# main.net
KiCad netlist of a schematic drawn in Altium Designer
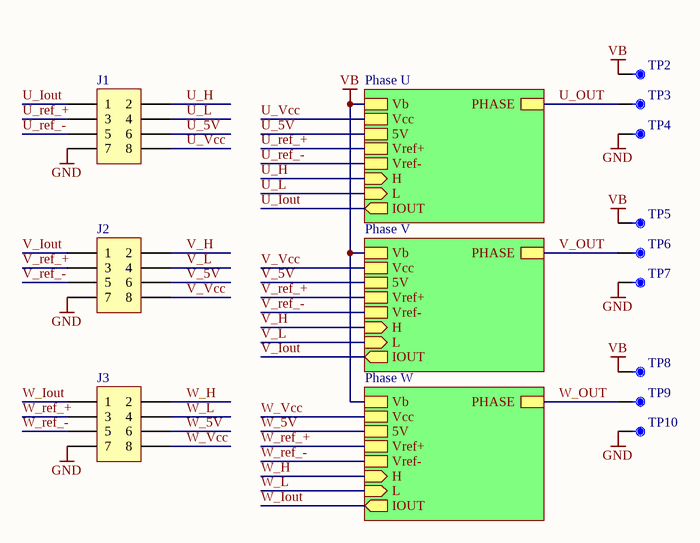
[diagram p0: main.SchDoc]

(export (version "E")
  (design (tool "Eeschema 10.0.6"))
  (components
    (comp (ref "J1")
      (value "~")
      (footprint "HDR-SMD_8P-P2.54-V-M-R2-C4-LS8.0")
      (libsource (lib "Schlib1") (part "Header 8"))
    )
    (comp (ref "J2")
      (value "~")
      (footprint "HDR-SMD_8P-P2.54-V-M-R2-C4-LS8.0")
      (libsource (lib "Schlib1") (part "Header 8"))
    )
    (comp (ref "J3")
      (value "~")
      (footprint "HDR-SMD_8P-P2.54-V-M-R2-C4-LS8.0")
      (libsource (lib "Schlib1") (part "Header 8"))
    )
    (comp (ref "TP2")
      (value "~")
      (footprint "TP2030_SMD")
      (libsource (lib "Miscellaneous Devices") (part "TP_Dup1"))
    )
    (comp (ref "TP3")
      (value "~")
      (footprint "TP2030_SMD")
      (libsource (lib "Miscellaneous Devices") (part "TP_Dup1"))
    )
    (comp (ref "TP4")
      (value "~")
      (footprint "TP2030_SMD")
      (libsource (lib "Miscellaneous Devices") (part "TP_Dup1"))
    )
    (comp (ref "TP5")
      (value "~")
      (footprint "TP2030_SMD")
      (libsource (lib "Miscellaneous Devices") (part "TP_Dup1"))
    )
    (comp (ref "TP6")
      (value "~")
      (footprint "TP2030_SMD")
      (libsource (lib "Miscellaneous Devices") (part "TP_Dup1"))
    )
    (comp (ref "TP7")
      (value "~")
      (footprint "TP2030_SMD")
      (libsource (lib "Miscellaneous Devices") (part "TP_Dup1"))
    )
    (comp (ref "TP8")
      (value "~")
      (footprint "TP2030_SMD")
      (libsource (lib "Miscellaneous Devices") (part "TP_Dup1"))
    )
    (comp (ref "TP9")
      (value "~")
      (footprint "TP2030_SMD")
      (libsource (lib "Miscellaneous Devices") (part "TP_Dup1"))
    )
    (comp (ref "TP10")
      (value "~")
      (footprint "TP2030_SMD")
      (libsource (lib "Miscellaneous Devices") (part "TP_Dup1"))
    )
  )
  (nets
    (net (code "1") (name "/U_5V") (class "Default")
      (node (ref "J1") (pin "6") (pinfunction "6_6") (pintype "passive"))
    )
    (net (code "2") (name "/U_H") (class "Default")
      (node (ref "J1") (pin "2") (pinfunction "2_2") (pintype "passive"))
    )
    (net (code "3") (name "/U_Iout") (class "Default")
      (node (ref "J1") (pin "1") (pinfunction "1_1") (pintype "passive"))
    )
    (net (code "4") (name "/U_L") (class "Default")
      (node (ref "J1") (pin "4") (pinfunction "4_4") (pintype "passive"))
    )
    (net (code "5") (name "/U_OUT") (class "Default")
      (node (ref "TP3") (pin "1") (pinfunction "1_1") (pintype "passive"))
    )
    (net (code "6") (name "/U_Vcc") (class "Default")
      (node (ref "J1") (pin "8") (pinfunction "8_8") (pintype "passive"))
    )
    (net (code "7") (name "/U_ref_+") (class "Default")
      (node (ref "J1") (pin "3") (pinfunction "3_3") (pintype "passive"))
    )
    (net (code "8") (name "/U_ref_-") (class "Default")
      (node (ref "J1") (pin "5") (pinfunction "5_5") (pintype "passive"))
    )
    (net (code "9") (name "/V_5V") (class "Default")
      (node (ref "J2") (pin "6") (pinfunction "6_6") (pintype "passive"))
    )
    (net (code "10") (name "/V_H") (class "Default")
      (node (ref "J2") (pin "2") (pinfunction "2_2") (pintype "passive"))
    )
    (net (code "11") (name "/V_Iout") (class "Default")
      (node (ref "J2") (pin "1") (pinfunction "1_1") (pintype "passive"))
    )
    (net (code "12") (name "/V_L") (class "Default")
      (node (ref "J2") (pin "4") (pinfunction "4_4") (pintype "passive"))
    )
    (net (code "13") (name "/V_OUT") (class "Default")
      (node (ref "TP6") (pin "1") (pinfunction "1_1") (pintype "passive"))
    )
    (net (code "14") (name "/V_Vcc") (class "Default")
      (node (ref "J2") (pin "8") (pinfunction "8_8") (pintype "passive"))
    )
    (net (code "15") (name "/V_ref_+") (class "Default")
      (node (ref "J2") (pin "3") (pinfunction "3_3") (pintype "passive"))
    )
    (net (code "16") (name "/V_ref_-") (class "Default")
      (node (ref "J2") (pin "5") (pinfunction "5_5") (pintype "passive"))
    )
    (net (code "17") (name "/W_5V") (class "Default")
      (node (ref "J3") (pin "6") (pinfunction "6_6") (pintype "passive"))
    )
    (net (code "18") (name "/W_H") (class "Default")
      (node (ref "J3") (pin "2") (pinfunction "2_2") (pintype "passive"))
    )
    (net (code "19") (name "/W_Iout") (class "Default")
      (node (ref "J3") (pin "1") (pinfunction "1_1") (pintype "passive"))
    )
    (net (code "20") (name "/W_L") (class "Default")
      (node (ref "J3") (pin "4") (pinfunction "4_4") (pintype "passive"))
    )
    (net (code "21") (name "/W_OUT") (class "Default")
      (node (ref "TP9") (pin "1") (pinfunction "1_1") (pintype "passive"))
    )
    (net (code "22") (name "/W_Vcc") (class "Default")
      (node (ref "J3") (pin "8") (pinfunction "8_8") (pintype "passive"))
    )
    (net (code "23") (name "/W_ref_+") (class "Default")
      (node (ref "J3") (pin "3") (pinfunction "3_3") (pintype "passive"))
    )
    (net (code "24") (name "/W_ref_-") (class "Default")
      (node (ref "J3") (pin "5") (pinfunction "5_5") (pintype "passive"))
    )
    (net (code "25") (name "GND") (class "Default")
      (node (ref "J1") (pin "7") (pinfunction "7_7") (pintype "passive"))
      (node (ref "J2") (pin "7") (pinfunction "7_7") (pintype "passive"))
      (node (ref "J3") (pin "7") (pinfunction "7_7") (pintype "passive"))
      (node (ref "TP10") (pin "1") (pinfunction "1_1") (pintype "passive"))
      (node (ref "TP4") (pin "1") (pinfunction "1_1") (pintype "passive"))
      (node (ref "TP7") (pin "1") (pinfunction "1_1") (pintype "passive"))
    )
    (net (code "26") (name "VB") (class "Default")
      (node (ref "TP2") (pin "1") (pinfunction "1_1") (pintype "passive"))
      (node (ref "TP5") (pin "1") (pinfunction "1_1") (pintype "passive"))
      (node (ref "TP8") (pin "1") (pinfunction "1_1") (pintype "passive"))
    )
  )
)
